# bicyclelab-charger-2.net
KiCad netlist of a schematic drawn in EAGLE
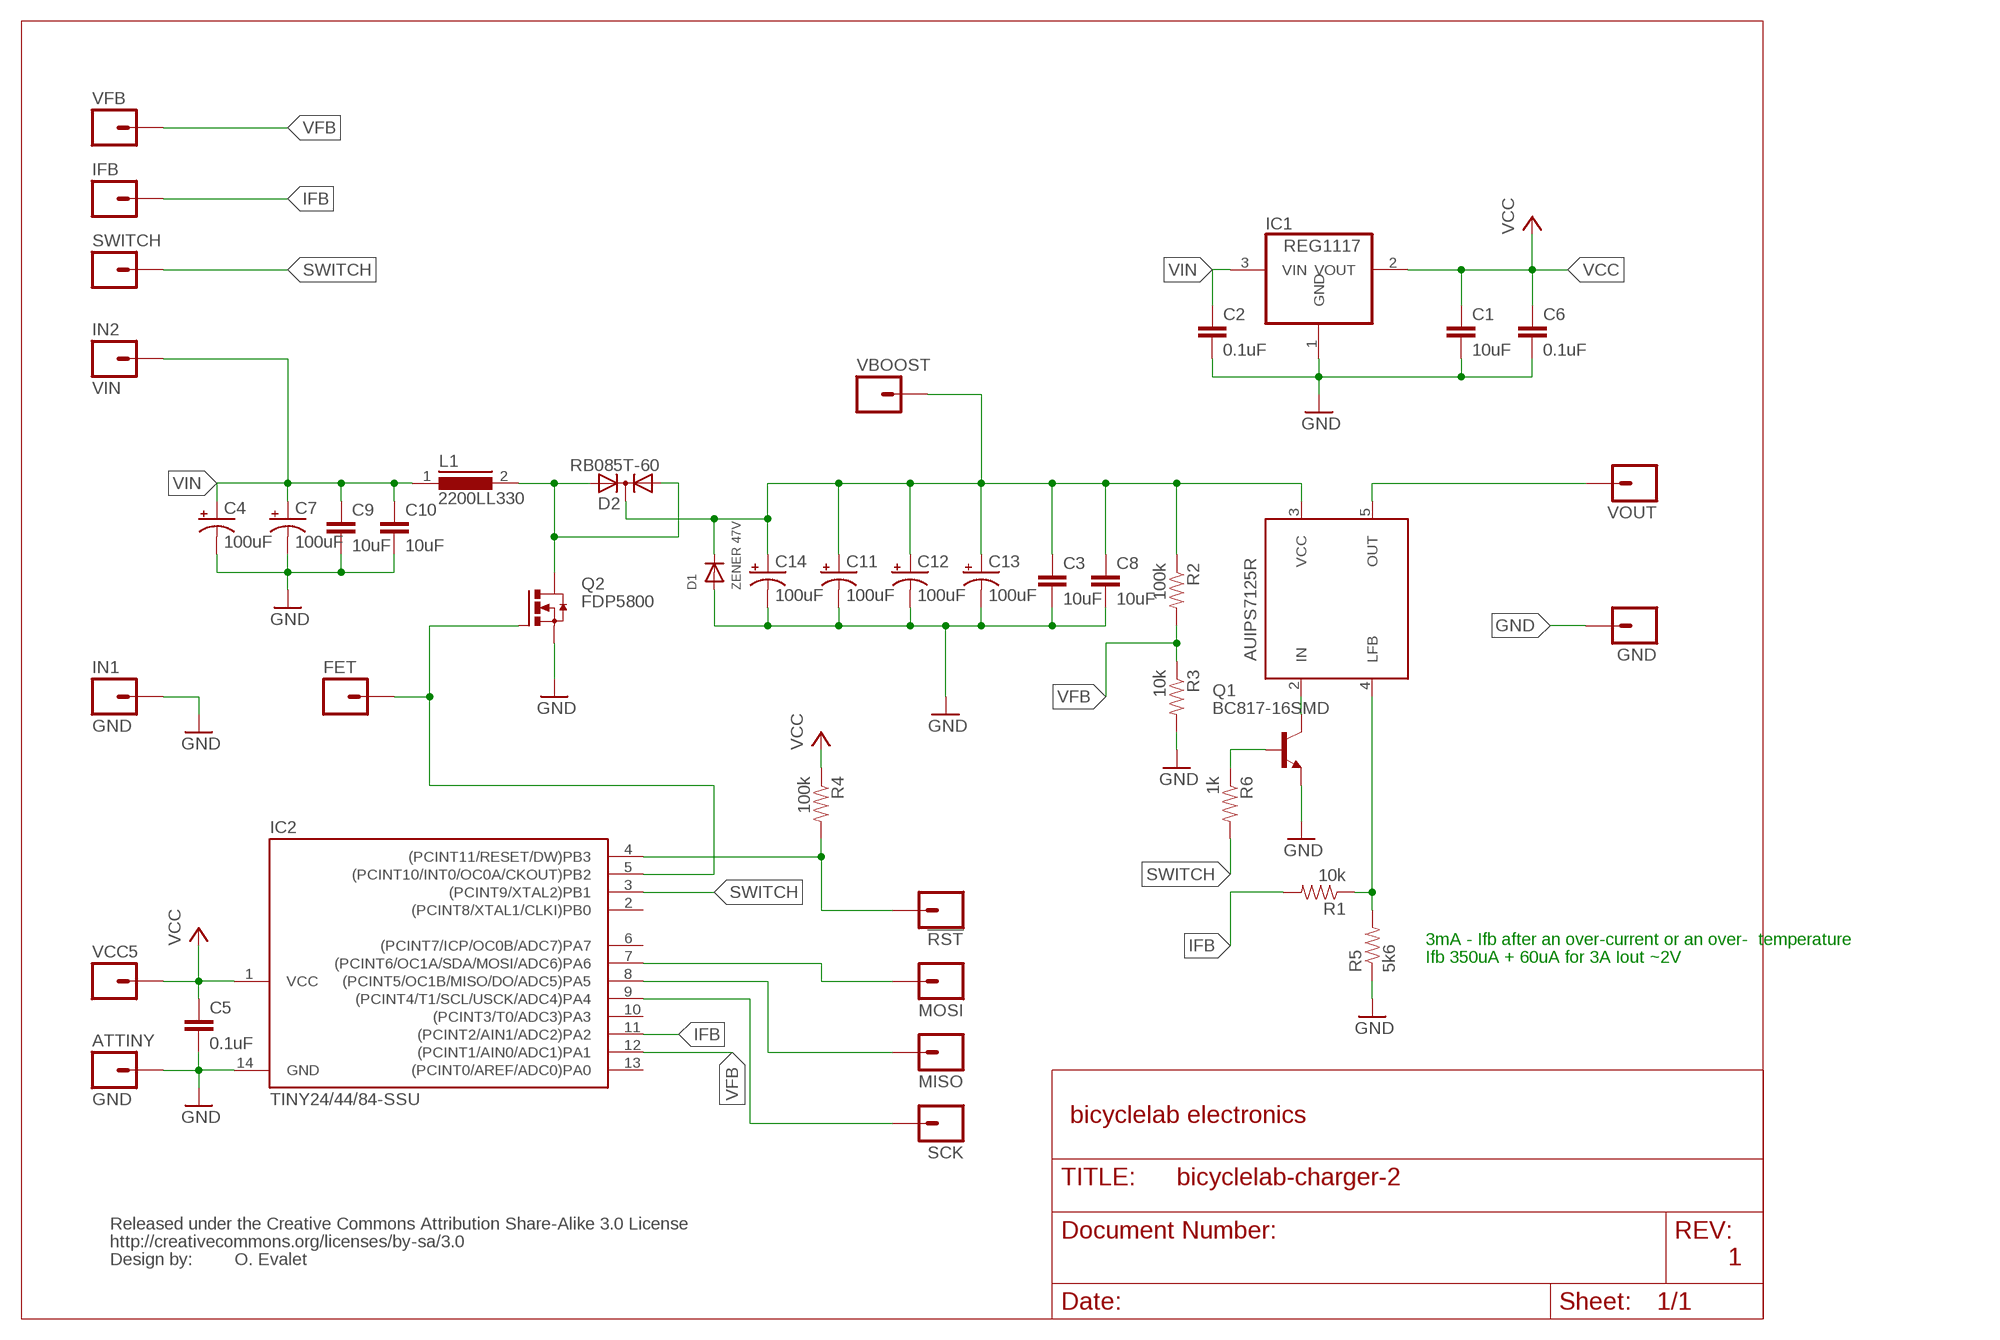
[diagram p0: schematic, sheet 1]

(export (version "E")
  (design (tool "Eeschema 10.0.6"))
  (components
    (comp (ref "!RST")
      (value "M01SMDNS")
      (footprint "eagle-import:1X01NS")
      (libsource (lib "eagle-import") (part "M01SMDNS"))
    )
    (comp (ref "ATTINY")
      (value "GND")
      (footprint "eagle-import:1X01NS")
      (libsource (lib "eagle-import") (part "M01SMDNS"))
    )
    (comp (ref "C1")
      (value "10uF")
      (footprint "eagle-import:1210")
      (libsource (lib "eagle-import") (part "CAP1210"))
    )
    (comp (ref "C2")
      (value "0.1uF")
      (footprint "eagle-import:0805")
      (libsource (lib "eagle-import") (part "CAP0805"))
    )
    (comp (ref "C3")
      (value "10uF")
      (footprint "eagle-import:1210")
      (libsource (lib "eagle-import") (part "CAP1210"))
    )
    (comp (ref "C4")
      (value "100uF")
      (footprint "eagle-import:PANASONIC_D")
      (libsource (lib "eagle-import") (part "CPOL-USD"))
    )
    (comp (ref "C5")
      (value "0.1uF")
      (footprint "eagle-import:0805")
      (libsource (lib "eagle-import") (part "CAP0805"))
    )
    (comp (ref "C6")
      (value "0.1uF")
      (footprint "eagle-import:0805")
      (libsource (lib "eagle-import") (part "CAP0805"))
    )
    (comp (ref "C7")
      (value "100uF")
      (footprint "eagle-import:PANASONIC_D")
      (libsource (lib "eagle-import") (part "CPOL-USD"))
    )
    (comp (ref "C8")
      (value "10uF")
      (footprint "eagle-import:1210")
      (libsource (lib "eagle-import") (part "CAP1210"))
    )
    (comp (ref "C9")
      (value "10uF")
      (footprint "eagle-import:1210")
      (libsource (lib "eagle-import") (part "CAP1210"))
    )
    (comp (ref "C10")
      (value "10uF")
      (footprint "eagle-import:1210")
      (libsource (lib "eagle-import") (part "CAP1210"))
    )
    (comp (ref "C11")
      (value "100uF")
      (footprint "eagle-import:PANASONIC_D")
      (libsource (lib "eagle-import") (part "CPOL-USD"))
    )
    (comp (ref "C12")
      (value "100uF")
      (footprint "eagle-import:PANASONIC_D")
      (libsource (lib "eagle-import") (part "CPOL-USD"))
    )
    (comp (ref "C13")
      (value "100uF")
      (footprint "eagle-import:PANASONIC_D")
      (libsource (lib "eagle-import") (part "CPOL-USD"))
    )
    (comp (ref "C14")
      (value "100uF")
      (footprint "eagle-import:PANASONIC_D")
      (libsource (lib "eagle-import") (part "CPOL-USD"))
    )
    (comp (ref "D1")
      (value "ZENER 47V")
      (footprint "eagle-import:SOD-123")
      (libsource (lib "eagle-import") (part "DIODESOD-123"))
    )
    (comp (ref "D2")
      (value "RB085T-60")
      (footprint "eagle-import:TO220AB")
      (libsource (lib "eagle-import") (part "DIODE-2AC|CATO220H"))
    )
    (comp (ref "FET")
      (value "M01SMDNS")
      (footprint "eagle-import:1X01NS")
      (libsource (lib "eagle-import") (part "M01SMDNS"))
    )
    (comp (ref "GND")
      (value "M01SMDNS")
      (footprint "eagle-import:1X01NS")
      (libsource (lib "eagle-import") (part "M01SMDNS"))
    )
    (comp (ref "IC1")
      (value "REG1117")
      (footprint "eagle-import:SOT223")
      (libsource (lib "eagle-import") (part "REG1117"))
    )
    (comp (ref "IC2")
      (value "TINY24/44/84-SSU")
      (footprint "eagle-import:SOIC14")
      (libsource (lib "eagle-import") (part "TINY24/44/84-SSU"))
    )
    (comp (ref "IFB")
      (value "M01SMDNS")
      (footprint "eagle-import:1X01NS")
      (libsource (lib "eagle-import") (part "M01SMDNS"))
    )
    (comp (ref "IN1")
      (value "GND")
      (footprint "eagle-import:1X01NS")
      (libsource (lib "eagle-import") (part "M01SMDNS"))
    )
    (comp (ref "IN2")
      (value "VIN")
      (footprint "eagle-import:1X01")
      (libsource (lib "eagle-import") (part "M01PTH"))
    )
    (comp (ref "L1")
      (value "2200LL330")
      (footprint "eagle-import:2200LL")
      (libsource (lib "eagle-import") (part "2200LL"))
    )
    (comp (ref "MISO")
      (value "M01SMDNS")
      (footprint "eagle-import:1X01NS")
      (libsource (lib "eagle-import") (part "M01SMDNS"))
    )
    (comp (ref "MOSI")
      (value "M01SMDNS")
      (footprint "eagle-import:1X01NS")
      (libsource (lib "eagle-import") (part "M01SMDNS"))
    )
    (comp (ref "Q1")
      (value "BC817-16SMD")
      (footprint "eagle-import:SOT23-BEC")
      (libsource (lib "eagle-import") (part "BC817SMD-16"))
    )
    (comp (ref "Q2")
      (value "FDP5800")
      (footprint "eagle-import:TO220AH")
      (libsource (lib "eagle-import") (part "IRF3704"))
    )
    (comp (ref "R1")
      (value "10k")
      (footprint "eagle-import:0805")
      (libsource (lib "eagle-import") (part "RESISTOR"))
    )
    (comp (ref "R2")
      (value "100k")
      (footprint "eagle-import:0805")
      (libsource (lib "eagle-import") (part "RESISTOR"))
    )
    (comp (ref "R3")
      (value "10k")
      (footprint "eagle-import:0805")
      (libsource (lib "eagle-import") (part "RESISTOR"))
    )
    (comp (ref "R4")
      (value "100k")
      (footprint "eagle-import:0805")
      (libsource (lib "eagle-import") (part "RESISTOR"))
    )
    (comp (ref "R5")
      (value "5k6")
      (footprint "eagle-import:0805")
      (libsource (lib "eagle-import") (part "RESISTOR"))
    )
    (comp (ref "R6")
      (value "1k")
      (footprint "eagle-import:0805")
      (libsource (lib "eagle-import") (part "RESISTOR"))
    )
    (comp (ref "SCK")
      (value "M01SMDNS")
      (footprint "eagle-import:1X01NS")
      (libsource (lib "eagle-import") (part "M01SMDNS"))
    )
    (comp (ref "SWITCH")
      (value "M01SMDNS")
      (footprint "eagle-import:1X01NS")
      (libsource (lib "eagle-import") (part "M01SMDNS"))
    )
    (comp (ref "U$5")
      (value "CREATIVE_COMMONS")
      (footprint "eagle-import:CREATIVE_COMMONS")
      (libsource (lib "eagle-import") (part "CREATIVE_COMMONS"))
    )
    (comp (ref "U$8")
      (value "AUIPS7125R")
      (footprint "eagle-import:DPAK-5")
      (libsource (lib "eagle-import") (part "AUIPS7125R"))
    )
    (comp (ref "VBOOST")
      (value "M01SMDNS")
      (footprint "eagle-import:1X01NS")
      (libsource (lib "eagle-import") (part "M01SMDNS"))
    )
    (comp (ref "VCC5")
      (value "M01PTH")
      (footprint "eagle-import:1X01")
      (libsource (lib "eagle-import") (part "M01PTH"))
    )
    (comp (ref "VFB")
      (value "M01SMDNS")
      (footprint "eagle-import:1X01NS")
      (libsource (lib "eagle-import") (part "M01SMDNS"))
    )
    (comp (ref "VOUT")
      (value "M01PTH")
      (footprint "eagle-import:1X01")
      (libsource (lib "eagle-import") (part "M01PTH"))
    )
  )
  (nets
    (net (code "1") (name "GND") (class "Default")
      (node (ref "ATTINY") (pin "1") (pinfunction "1_1") (pintype "passive"))
      (node (ref "C1") (pin "2") (pinfunction "2_2") (pintype "passive"))
      (node (ref "C10") (pin "2") (pinfunction "2_2") (pintype "passive"))
      (node (ref "C11") (pin "-") (pinfunction "-_-") (pintype "passive"))
      (node (ref "C12") (pin "-") (pinfunction "-_-") (pintype "passive"))
      (node (ref "C13") (pin "-") (pinfunction "-_-") (pintype "passive"))
      (node (ref "C14") (pin "-") (pinfunction "-_-") (pintype "passive"))
      (node (ref "C2") (pin "2") (pinfunction "2_2") (pintype "passive"))
      (node (ref "C3") (pin "2") (pinfunction "2_2") (pintype "passive"))
      (node (ref "C4") (pin "-") (pinfunction "-_-") (pintype "passive"))
      (node (ref "C5") (pin "2") (pinfunction "2_2") (pintype "passive"))
      (node (ref "C6") (pin "2") (pinfunction "2_2") (pintype "passive"))
      (node (ref "C7") (pin "-") (pinfunction "-_-") (pintype "passive"))
      (node (ref "C8") (pin "2") (pinfunction "2_2") (pintype "passive"))
      (node (ref "C9") (pin "2") (pinfunction "2_2") (pintype "passive"))
      (node (ref "D1") (pin "A") (pinfunction "A_A") (pintype "passive"))
      (node (ref "GND") (pin "1") (pinfunction "1_1") (pintype "passive"))
      (node (ref "IC1") (pin "1") (pinfunction "GND_1") (pintype "power_in"))
      (node (ref "IC2") (pin "14") (pinfunction "GND_14") (pintype "power_in"))
      (node (ref "IN1") (pin "1") (pinfunction "1_1") (pintype "passive"))
      (node (ref "Q1") (pin "E") (pinfunction "E_E") (pintype "passive"))
      (node (ref "Q2") (pin "E") (pinfunction "S_E") (pintype "passive"))
      (node (ref "R3") (pin "2") (pinfunction "2_2") (pintype "passive"))
      (node (ref "R5") (pin "1") (pinfunction "1_1") (pintype "passive"))
    )
    (net (code "2") (name "IFB") (class "Default")
      (node (ref "IC2") (pin "11") (pinfunction "(PCINT2/AIN1/ADC2)PA2_11") (pintype "bidirectional"))
      (node (ref "IFB") (pin "1") (pinfunction "1_1") (pintype "passive"))
      (node (ref "R1") (pin "2") (pinfunction "2_2") (pintype "passive"))
    )
    (net (code "3") (name "Net-(IC2-(PCINT4{slash}T1{slash}SCL{slash}USCK{slash}ADC4)PA4)") (class "Default")
      (node (ref "IC2") (pin "9") (pinfunction "(PCINT4/T1/SCL/USCK/ADC4)PA4_9") (pintype "bidirectional"))
      (node (ref "SCK") (pin "1") (pinfunction "1_1") (pintype "passive"))
    )
    (net (code "4") (name "Net-(IC2-(PCINT5{slash}OC1B{slash}MISO{slash}DO{slash}ADC5)PA5)") (class "Default")
      (node (ref "IC2") (pin "8") (pinfunction "(PCINT5/OC1B/MISO/DO/ADC5)PA5_8") (pintype "bidirectional"))
      (node (ref "MISO") (pin "1") (pinfunction "1_1") (pintype "passive"))
    )
    (net (code "5") (name "Net-(IC2-(PCINT6{slash}OC1A{slash}SDA{slash}MOSI{slash}ADC6)PA6)") (class "Default")
      (node (ref "IC2") (pin "7") (pinfunction "(PCINT6/OC1A/SDA/MOSI/ADC6)PA6_7") (pintype "bidirectional"))
      (node (ref "MOSI") (pin "1") (pinfunction "1_1") (pintype "passive"))
    )
    (net (code "6") (name "Net-(IC2-(PCINT10{slash}INT0{slash}OC0A{slash}CKOUT)PB2)") (class "Default")
      (node (ref "FET") (pin "1") (pinfunction "1_1") (pintype "passive"))
      (node (ref "IC2") (pin "5") (pinfunction "(PCINT10/INT0/OC0A/CKOUT)PB2_5") (pintype "bidirectional"))
      (node (ref "Q2") (pin "B") (pinfunction "G_B") (pintype "passive"))
    )
    (net (code "7") (name "Net-(IC2-(PCINT11{slash}RESET{slash}DW)PB3)") (class "Default")
      (node (ref "!RST") (pin "1") (pinfunction "1_1") (pintype "passive"))
      (node (ref "IC2") (pin "4") (pinfunction "(PCINT11/RESET/DW)PB3_4") (pintype "bidirectional"))
      (node (ref "R4") (pin "2") (pinfunction "2_2") (pintype "passive"))
    )
    (net (code "8") (name "Net-(Q1-PadB)") (class "Default")
      (node (ref "Q1") (pin "B") (pinfunction "B_B") (pintype "passive"))
      (node (ref "R6") (pin "1") (pinfunction "1_1") (pintype "passive"))
    )
    (net (code "9") (name "Net-(Q2-D)") (class "Default")
      (node (ref "D2") (pin "A1") (pinfunction "A1_A1") (pintype "passive"))
      (node (ref "D2") (pin "A2") (pinfunction "A2_A2") (pintype "passive"))
      (node (ref "L1") (pin "2") (pinfunction "2_2") (pintype "passive"))
      (node (ref "Q2") (pin "C") (pinfunction "D_C") (pintype "passive"))
    )
    (net (code "10") (name "Net-(U$8-IN)") (class "Default")
      (node (ref "Q1") (pin "C") (pinfunction "C_C") (pintype "passive"))
      (node (ref "U$8") (pin "2") (pinfunction "IN_2") (pintype "input"))
    )
    (net (code "11") (name "Net-(U$8-LFB)") (class "Default")
      (node (ref "R1") (pin "1") (pinfunction "1_1") (pintype "passive"))
      (node (ref "R5") (pin "2") (pinfunction "2_2") (pintype "passive"))
      (node (ref "U$8") (pin "4") (pinfunction "LFB_4") (pintype "output"))
    )
    (net (code "12") (name "Net-(U$8-OUT)") (class "Default")
      (node (ref "U$8") (pin "5") (pinfunction "OUT_5") (pintype "output"))
      (node (ref "VOUT") (pin "1") (pinfunction "1_1") (pintype "passive"))
    )
    (net (code "13") (name "Net-(U$8-VCC)") (class "Default")
      (node (ref "C11") (pin "+") (pinfunction "+_+") (pintype "passive"))
      (node (ref "C12") (pin "+") (pinfunction "+_+") (pintype "passive"))
      (node (ref "C13") (pin "+") (pinfunction "+_+") (pintype "passive"))
      (node (ref "C14") (pin "+") (pinfunction "+_+") (pintype "passive"))
      (node (ref "C3") (pin "1") (pinfunction "1_1") (pintype "passive"))
      (node (ref "C8") (pin "1") (pinfunction "1_1") (pintype "passive"))
      (node (ref "D1") (pin "C") (pinfunction "C_C") (pintype "passive"))
      (node (ref "D2") (pin "C") (pinfunction "C_C") (pintype "passive"))
      (node (ref "R2") (pin "1") (pinfunction "1_1") (pintype "passive"))
      (node (ref "U$8") (pin "3") (pinfunction "VCC_3") (pintype "input"))
      (node (ref "VBOOST") (pin "1") (pinfunction "1_1") (pintype "passive"))
    )
    (net (code "14") (name "SWITCH") (class "Default")
      (node (ref "IC2") (pin "3") (pinfunction "(PCINT9/XTAL2)PB1_3") (pintype "bidirectional"))
      (node (ref "R6") (pin "2") (pinfunction "2_2") (pintype "passive"))
      (node (ref "SWITCH") (pin "1") (pinfunction "1_1") (pintype "passive"))
    )
    (net (code "15") (name "VCC") (class "Default")
      (node (ref "C1") (pin "1") (pinfunction "1_1") (pintype "passive"))
      (node (ref "C5") (pin "1") (pinfunction "1_1") (pintype "passive"))
      (node (ref "C6") (pin "1") (pinfunction "1_1") (pintype "passive"))
      (node (ref "IC1") (pin "2") (pinfunction "VOUT_2") (pintype "output"))
      (node (ref "IC2") (pin "1") (pinfunction "VCC_1") (pintype "power_in"))
      (node (ref "R4") (pin "1") (pinfunction "1_1") (pintype "passive"))
      (node (ref "VCC5") (pin "1") (pinfunction "1_1") (pintype "passive"))
    )
    (net (code "16") (name "VFB") (class "Default")
      (node (ref "IC2") (pin "12") (pinfunction "(PCINT1/AIN0/ADC1)PA1_12") (pintype "bidirectional"))
      (node (ref "R2") (pin "2") (pinfunction "2_2") (pintype "passive"))
      (node (ref "R3") (pin "1") (pinfunction "1_1") (pintype "passive"))
      (node (ref "VFB") (pin "1") (pinfunction "1_1") (pintype "passive"))
    )
    (net (code "17") (name "VIN") (class "Default")
      (node (ref "C10") (pin "1") (pinfunction "1_1") (pintype "passive"))
      (node (ref "C2") (pin "1") (pinfunction "1_1") (pintype "passive"))
      (node (ref "C4") (pin "+") (pinfunction "+_+") (pintype "passive"))
      (node (ref "C7") (pin "+") (pinfunction "+_+") (pintype "passive"))
      (node (ref "C9") (pin "1") (pinfunction "1_1") (pintype "passive"))
      (node (ref "IC1") (pin "3") (pinfunction "VIN_3") (pintype "input"))
      (node (ref "IN2") (pin "1") (pinfunction "1_1") (pintype "passive"))
      (node (ref "L1") (pin "1") (pinfunction "1_1") (pintype "passive"))
    )
    (net (code "18") (name "unconnected-(IC2-(PCINT0{slash}AREF{slash}ADC0)PA0-Pad13)") (class "Default")
      (node (ref "IC2") (pin "13") (pinfunction "(PCINT0/AREF/ADC0)PA0_13") (pintype "bidirectional"))
    )
    (net (code "19") (name "unconnected-(IC2-(PCINT3{slash}T0{slash}ADC3)PA3-Pad10)") (class "Default")
      (node (ref "IC2") (pin "10") (pinfunction "(PCINT3/T0/ADC3)PA3_10") (pintype "bidirectional"))
    )
    (net (code "20") (name "unconnected-(IC2-(PCINT7{slash}ICP{slash}OC0B{slash}ADC7)PA7-Pad6)") (class "Default")
      (node (ref "IC2") (pin "6") (pinfunction "(PCINT7/ICP/OC0B/ADC7)PA7_6") (pintype "bidirectional"))
    )
    (net (code "21") (name "unconnected-(IC2-(PCINT8{slash}XTAL1{slash}CLKI)PB0-Pad2)") (class "Default")
      (node (ref "IC2") (pin "2") (pinfunction "(PCINT8/XTAL1/CLKI)PB0_2") (pintype "bidirectional"))
    )
    (net (code "22") (name "unconnected-(U$8-NC-Pad1)") (class "Default")
      (node (ref "U$8") (pin "1") (pinfunction "NC_1") (pintype "no_connect"))
    )
  )
)
